# ProProject_PetCareSTM32_MiniSTM32_2024-0.net
KiCad netlist of a schematic drawn in EasyEDA Pro
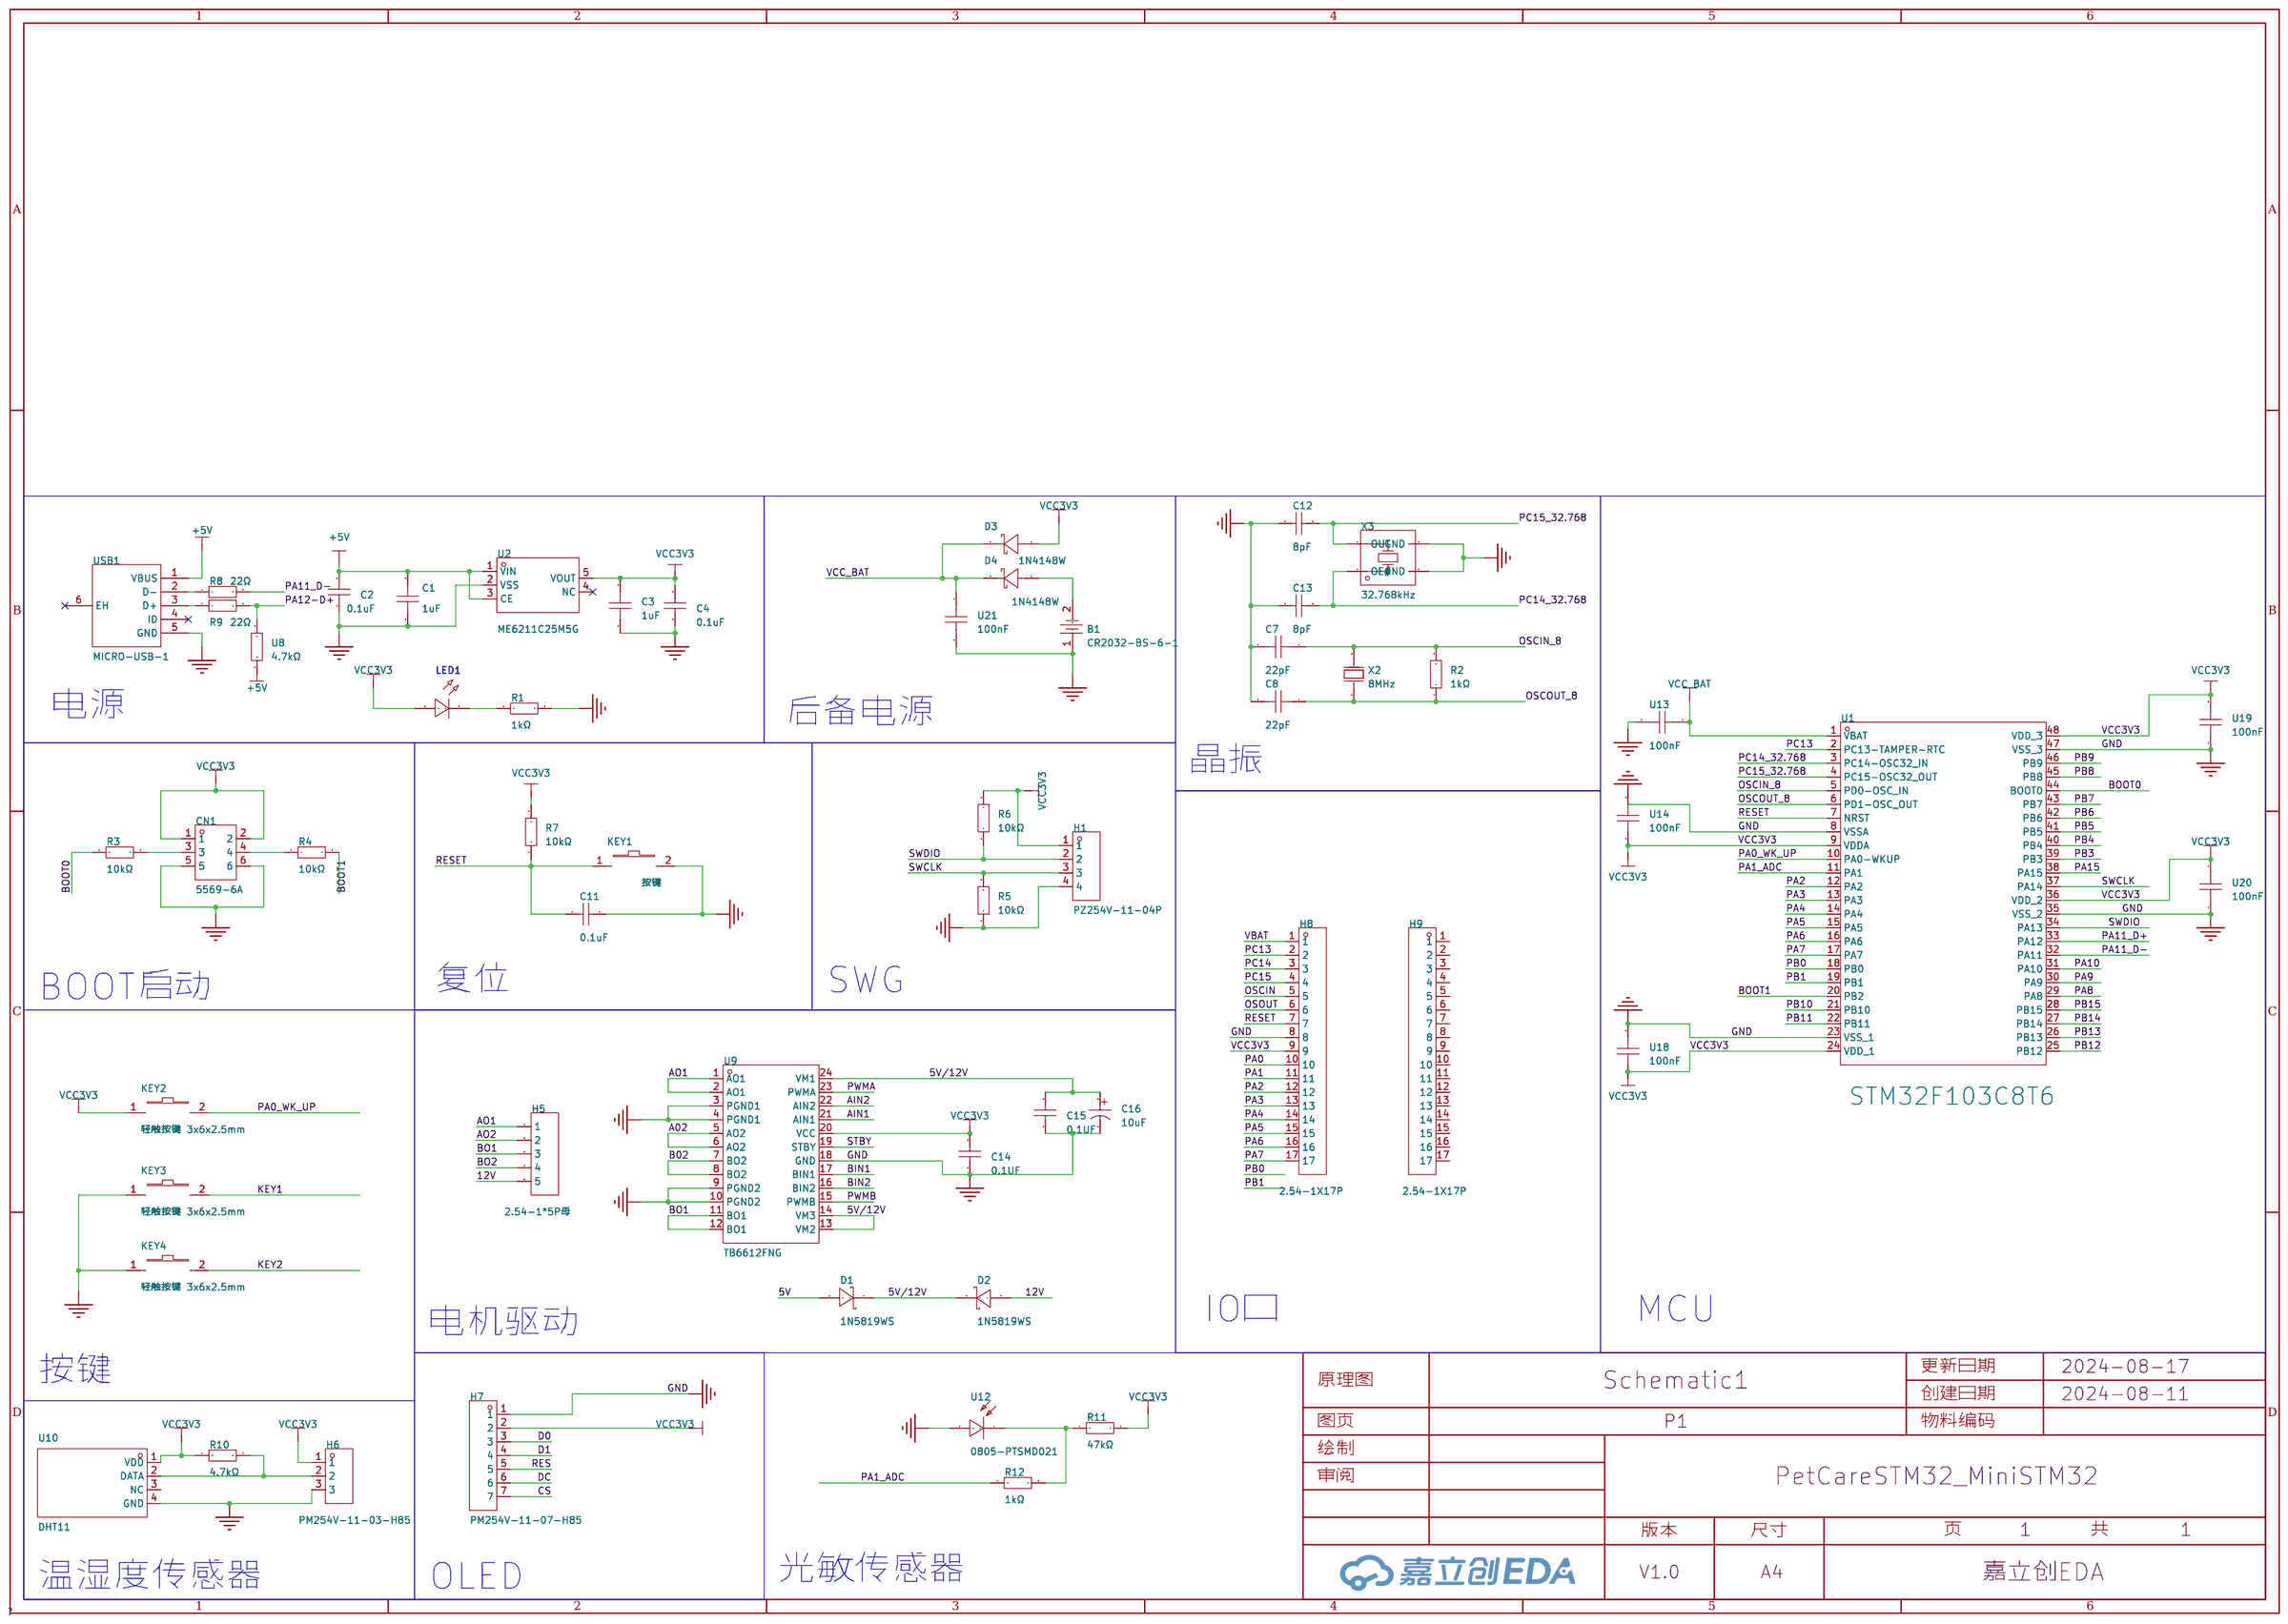
[diagram p0: schematic sheet]

(export (version "E")
  (design (tool "Eeschema 10.0.6"))
  (components
    (comp (ref "B1")
      (value "CR2032-BS-6-1")
      (footprint "easyedapro:BAT-TH_CR2032-BS-6-1")
      (description "连接器类型:电池底座;适用电池规格:CR2032;工作温度范围:-;")
      (fields (field (name "Manufacturer") "Q&J"))
      (libsource (lib "easyedapro") (part "CR2032-BS-6-1"))
    )
    (comp (ref "C1")
      (value "1uF")
      (footprint "easyedapro:C0603")
      (description "容值:1uF;精度:±10%;额定电压:50V;材质(温度系数):X5R;")
      (fields
        (field (name "Manufacturer Part") "CL10A105KB8NNNC")
        (field (name "Manufacturer") "SAMSUNG(三星)")
      )
      (libsource (lib "easyedapro") (part "CL10A105KB8NNNC"))
    )
    (comp (ref "C2")
      (value "0.1uF")
      (footprint "easyedapro:C0603")
      (libsource (lib "easyedapro") (part "CAPCER0.1UF16VX5R0603,CAPCER0.1UF25VX5R0603,CAPCER0.1UF16VX7R0603"))
    )
    (comp (ref "C3")
      (value "1uF")
      (footprint "easyedapro:C0603")
      (description "容值:1uF;精度:±10%;额定电压:50V;材质(温度系数):X5R;")
      (fields
        (field (name "Manufacturer Part") "CL10A105KB8NNNC")
        (field (name "Manufacturer") "SAMSUNG(三星)")
      )
      (libsource (lib "easyedapro") (part "CL10A105KB8NNNC"))
    )
    (comp (ref "C4")
      (value "0.1uF")
      (footprint "easyedapro:C0603")
      (libsource (lib "easyedapro") (part "CAPCER0.1UF16VX5R0603,CAPCER0.1UF25VX5R0603,CAPCER0.1UF16VX7R0603"))
    )
    (comp (ref "C7")
      (value "22pF")
      (footprint "easyedapro:C0603")
      (description "容值:22pF;精度:±5%;额定电压:50V;材质(温度系数):C0G;")
      (fields
        (field (name "Manufacturer Part") "CL10C220JB81PNC")
        (field (name "Manufacturer") "SAMSUNG(三星)")
      )
      (libsource (lib "easyedapro") (part "CL10C220JB81PNC"))
    )
    (comp (ref "C8")
      (value "22pF")
      (footprint "easyedapro:C0603")
      (description "容值:22pF;精度:±5%;额定电压:50V;材质(温度系数):C0G;")
      (fields
        (field (name "Manufacturer Part") "CL10C220JB81PNC")
        (field (name "Manufacturer") "SAMSUNG(三星)")
      )
      (libsource (lib "easyedapro") (part "CL10C220JB81PNC"))
    )
    (comp (ref "C11")
      (value "0.1uF")
      (footprint "easyedapro:C0603")
      (libsource (lib "easyedapro") (part "CAPCER0.1UF16VX5R0603,CAPCER0.1UF25VX5R0603,CAPCER0.1UF16VX7R0603"))
    )
    (comp (ref "C12")
      (value "8pF")
      (footprint "easyedapro:C0603")
      (description "容值:8pF;额定电压:50V;材质(温度系数):C0G;")
      (fields (field (name "Manufacturer Part") "0603CG8R0C500NT") (field (name "Manufacturer") "FH(风华)"))
      (libsource (lib "easyedapro") (part "0603CG8R0C500NT_C36508"))
    )
    (comp (ref "C13")
      (value "8pF")
      (footprint "easyedapro:C0603")
      (description "容值:8pF;额定电压:50V;材质(温度系数):C0G;")
      (fields (field (name "Manufacturer Part") "0603CG8R0C500NT") (field (name "Manufacturer") "FH(风华)"))
      (libsource (lib "easyedapro") (part "0603CG8R0C500NT_C36508"))
    )
    (comp (ref "C14")
      (value "0.1UF")
      (footprint "easyedapro:C0603")
      (libsource (lib "easyedapro") (part "CAPCER0.1UF16VX5R0603,CAPCER0.1UF25VX5R0603,CAPCER0.1UF16VX7R0603"))
    )
    (comp (ref "C15")
      (value "0.1UF")
      (footprint "easyedapro:C0603")
      (libsource (lib "easyedapro") (part "CAPCER0.1UF16VX5R0603,CAPCER0.1UF25VX5R0603,CAPCER0.1UF16VX7R0603"))
    )
    (comp (ref "C16")
      (value "10uF")
      (footprint "easyedapro:CAP-TH_BD5.0-P2.00-D0.8-FD")
      (description "容值:10uF;精度:±20%;额定电压:25V;")
      (fields (field (name "Manufacturer Part") "KF100M025C110A") (field (name "Manufacturer") "CapXon(丰宾)"))
      (libsource (lib "easyedapro") (part "KF100M025C110A"))
    )
    (comp (ref "CN1")
      (value "5569-6A")
      (footprint "easyedapro:CONN-TH_6P-P4.20_5569-6A-1")
      (libsource (lib "easyedapro") (part "5569-6A"))
    )
    (comp (ref "D1")
      (value "1N5819WS")
      (footprint "easyedapro:SOD-323_L1.8-W1.3-LS2.5-RD")
      (description "正向压降(Vf):600mV@1A;直流反向耐压(Vr):40V;平均整流电流(Io):1A;")
      (fields (field (name "Manufacturer") "Hottech(合科泰)"))
      (libsource (lib "easyedapro") (part "1N5819WS"))
    )
    (comp (ref "D2")
      (value "1N5819WS")
      (footprint "easyedapro:SOD-323_L1.8-W1.3-LS2.5-RD")
      (description "正向压降(Vf):600mV@1A;直流反向耐压(Vr):40V;平均整流电流(Io):1A;")
      (fields (field (name "Manufacturer") "Hottech(合科泰)"))
      (libsource (lib "easyedapro") (part "1N5819WS"))
    )
    (comp (ref "D3")
      (value "1N4148W")
      (footprint "easyedapro:SOD-123_L2.7-W1.6-LS3.7-FD")
      (description "二极管配置:独立式;正向压降(Vf):1.25V@150mA;直流反向耐压(Vr):100V;平均整流电流(Io):150mA;功率:400mW;反向恢复时间(trr):4ns;")
      (fields (field (name "Manufacturer") "宏迦橙"))
      (libsource (lib "easyedapro") (part "1N4148W_C7420318"))
    )
    (comp (ref "D4")
      (value "1N4148W")
      (footprint "easyedapro:SOD-123_L2.7-W1.6-LS3.7-FD")
      (description "二极管配置:独立式;正向压降(Vf):1.25V@150mA;直流反向耐压(Vr):100V;平均整流电流(Io):150mA;功率:400mW;反向恢复时间(trr):4ns;")
      (fields (field (name "Manufacturer") "宏迦橙"))
      (libsource (lib "easyedapro") (part "1N4148W_C7420318"))
    )
    (comp (ref "H1")
      (value "PZ254V-11-04P")
      (footprint "easyedapro:HDR-TH_4P-P2.54-V-M")
      (fields (field (name "Manufacturer") "XFCN(兴飞)"))
      (libsource (lib "easyedapro") (part "PZ254V-11-04P_C2691448"))
    )
    (comp (ref "H5")
      (value "2.54-1*5P母")
      (footprint "easyedapro:HDR-TH_5P-P2.54-V-F")
      (description "插孔结构:1x5P;间距:2.54mm;行距:-;安装类型:直插;排数:单排;总孔位数:5P;塑高:-;触头材质:-;触头镀层:-;")
      (fields (field (name "Manufacturer") "BOOMELE(博穆精密)"))
      (libsource (lib "easyedapro") (part "Header-Female-2.54_1x5"))
    )
    (comp (ref "H6")
      (value "PM254V-11-03-H85")
      (footprint "easyedapro:HDR-TH_3P-P2.54-V-F")
      (description "插孔结构:1x3P;间距:2.54mm;行距:-;安装类型:直插;排数:单排;总孔位数:3P;塑高:-;触头材质:黄铜;触头镀层:-;")
      (fields (field (name "Manufacturer") "XFCN(兴飞)"))
      (libsource (lib "easyedapro") (part "PM254V-11-03-H85"))
    )
    (comp (ref "H7")
      (value "PM254V-11-07-H85")
      (footprint "easyedapro:HDR-TH_7P-P2.54-V-F")
      (fields (field (name "Manufacturer") "XFCN(兴飞)"))
      (libsource (lib "easyedapro") (part "PM254V-11-07-H85"))
    )
    (comp (ref "H8")
      (value "2.54-1X17P")
      (footprint "easyedapro:HDR-TH_17P-P2.54-V-M")
      (fields (field (name "Manufacturer") "kinghelm(金航标)"))
      (libsource (lib "easyedapro") (part "KH-2.54PH180-1X17P-L11.5"))
    )
    (comp (ref "H9")
      (value "2.54-1X17P")
      (footprint "easyedapro:HDR-TH_17P-P2.54-V-M")
      (fields (field (name "Manufacturer") "kinghelm(金航标)"))
      (libsource (lib "easyedapro") (part "KH-2.54PH180-1X17P-L11.5"))
    )
    (comp (ref "KEY1")
      (value "按键")
      (footprint "easyedapro:SW-SMD_L6.0-W3.6-LS8.0")
      (libsource (lib "easyedapro") (part "3x6x2.5mm"))
    )
    (comp (ref "KEY2")
      (value "轻触按键 3x6x2.5mm")
      (footprint "easyedapro:SW-SMD_L6.0-W3.6-LS8.0")
      (libsource (lib "easyedapro") (part "3x6x2.5mm"))
    )
    (comp (ref "KEY3")
      (value "轻触按键 3x6x2.5mm")
      (footprint "easyedapro:SW-SMD_L6.0-W3.6-LS8.0")
      (libsource (lib "easyedapro") (part "3x6x2.5mm"))
    )
    (comp (ref "KEY4")
      (value "轻触按键 3x6x2.5mm")
      (footprint "easyedapro:SW-SMD_L6.0-W3.6-LS8.0")
      (libsource (lib "easyedapro") (part "3x6x2.5mm"))
    )
    (comp (ref "LED1")
      (value "~")
      (footprint "easyedapro:LED_0805")
      (libsource (lib "easyedapro") (part "LED_B"))
    )
    (comp (ref "R1")
      (value "1kΩ")
      (footprint "easyedapro:R0603")
      (description "电阻类型:厚膜电阻;阻值:1kΩ;精度:±1%;功率:100mW;最大工作电压:75V;温度系数:±100ppm/°C;")
      (fields (field (name "Manufacturer Part") "RC0603FR-071KL") (field (name "Manufacturer") "YAGEO(国巨)"))
      (libsource (lib "easyedapro") (part "RC0603FR-071KL"))
    )
    (comp (ref "R2")
      (value "1kΩ")
      (footprint "easyedapro:R0603")
      (description "电阻类型:厚膜电阻;阻值:1kΩ;精度:±0.5%;功率:100mW;最大工作电压:75V;温度系数:±100ppm/°C;")
      (fields
        (field (name "Manufacturer Part") "0603WAD1001T5E")
        (field (name "Manufacturer") "UNI-ROYAL(厚声)")
      )
      (libsource (lib "easyedapro") (part "0603WAD1001T5E"))
    )
    (comp (ref "R3")
      (value "10kΩ")
      (footprint "easyedapro:R0603")
      (description "电阻类型:厚膜电阻;阻值:10kΩ;精度:±1%;功率:100mW;最大工作电压:75V;温度系数:±100ppm/°C;")
      (fields
        (field (name "Manufacturer Part") "0603WAF1002T5E")
        (field (name "Manufacturer") "UNI-ROYAL(厚声)")
      )
      (libsource (lib "easyedapro") (part "0603WAF1002T5E"))
    )
    (comp (ref "R4")
      (value "10kΩ")
      (footprint "easyedapro:R0603")
      (description "电阻类型:厚膜电阻;阻值:10kΩ;精度:±1%;功率:100mW;最大工作电压:75V;温度系数:±100ppm/°C;")
      (fields
        (field (name "Manufacturer Part") "0603WAF1002T5E")
        (field (name "Manufacturer") "UNI-ROYAL(厚声)")
      )
      (libsource (lib "easyedapro") (part "0603WAF1002T5E"))
    )
    (comp (ref "R5")
      (value "10kΩ")
      (footprint "easyedapro:R0603")
      (description "电阻类型:厚膜电阻;阻值:10kΩ;精度:±1%;功率:100mW;最大工作电压:75V;温度系数:±100ppm/°C;")
      (fields
        (field (name "Manufacturer Part") "0603WAF1002T5E")
        (field (name "Manufacturer") "UNI-ROYAL(厚声)")
      )
      (libsource (lib "easyedapro") (part "0603WAF1002T5E"))
    )
    (comp (ref "R6")
      (value "10kΩ")
      (footprint "easyedapro:R0603")
      (description "电阻类型:厚膜电阻;阻值:10kΩ;精度:±1%;功率:100mW;最大工作电压:75V;温度系数:±100ppm/°C;")
      (fields
        (field (name "Manufacturer Part") "0603WAF1002T5E")
        (field (name "Manufacturer") "UNI-ROYAL(厚声)")
      )
      (libsource (lib "easyedapro") (part "0603WAF1002T5E"))
    )
    (comp (ref "R7")
      (value "10kΩ")
      (footprint "easyedapro:R0603")
      (description "电阻类型:厚膜电阻;阻值:10kΩ;精度:±1%;功率:100mW;最大工作电压:75V;温度系数:±100ppm/°C;")
      (fields
        (field (name "Manufacturer Part") "0603WAF1002T5E")
        (field (name "Manufacturer") "UNI-ROYAL(厚声)")
      )
      (libsource (lib "easyedapro") (part "0603WAF1002T5E"))
    )
    (comp (ref "R8")
      (value "22Ω")
      (footprint "easyedapro:R0805")
      (description "电阻类型:薄膜电阻;阻值:22Ω;精度:±1%;功率:250mW;最大工作电压:150V;温度系数:±25ppm/°C;")
      (fields
        (field (name "Manufacturer Part") "TC0525F220JT5E")
        (field (name "Manufacturer") "UNI-ROYAL(厚声)")
      )
      (libsource (lib "easyedapro") (part "TC0525F220JT5E"))
    )
    (comp (ref "R9")
      (value "22Ω")
      (footprint "easyedapro:R0805")
      (description "电阻类型:薄膜电阻;阻值:22Ω;精度:±1%;功率:250mW;最大工作电压:150V;温度系数:±25ppm/°C;")
      (fields
        (field (name "Manufacturer Part") "TC0525F220JT5E")
        (field (name "Manufacturer") "UNI-ROYAL(厚声)")
      )
      (libsource (lib "easyedapro") (part "TC0525F220JT5E"))
    )
    (comp (ref "R10")
      (value "4.7kΩ")
      (footprint "easyedapro:R1206")
      (description "电阻类型:厚膜电阻;阻值:4.7kΩ;精度:±1%;功率:250mW;最大工作电压:200V;温度系数:±100ppm/°C;")
      (fields
        (field (name "Manufacturer Part") "1206W4F4701T5E")
        (field (name "Manufacturer") "UNI-ROYAL(厚声)")
      )
      (libsource (lib "easyedapro") (part "1206W4F4701T5E"))
    )
    (comp (ref "R11")
      (value "47kΩ")
      (footprint "easyedapro:R0805")
      (description "电阻类型:厚膜电阻;阻值:47kΩ;精度:±1%;功率:125mW;最大工作电压:150V;温度系数:±100ppm/°C;")
      (fields
        (field (name "Manufacturer Part") "0805W8F4702T5E")
        (field (name "Manufacturer") "UNI-ROYAL(厚声)")
      )
      (libsource (lib "easyedapro") (part "0805W8F4702T5E"))
    )
    (comp (ref "R12")
      (value "1kΩ")
      (footprint "easyedapro:R0603")
      (description "电阻类型:厚膜电阻;阻值:1kΩ;精度:±1%;功率:100mW;最大工作电压:75V;温度系数:±100ppm/°C;")
      (fields (field (name "Manufacturer Part") "RC0603FR-071KL") (field (name "Manufacturer") "YAGEO(国巨)"))
      (libsource (lib "easyedapro") (part "RC0603FR-071KL"))
    )
    (comp (ref "U1")
      (value "STM32F103C8T6")
      (footprint "easyedapro:LQFP-48_L7.0-W7.0-P0.50-LS9.0-BL")
      (description "CPU内核:ARM-M3;程序存储容量:64KB;RAM总容量:20KB;GPIO端口数量:37;工作电压范围:2V~3.6V;CPU最大主频:72MHz;程序存储器类型:FLASH;")
      (fields (field (name "Manufacturer") "ST(意法半导体)"))
      (libsource (lib "easyedapro") (part "STM32F103C8T6"))
    )
    (comp (ref "U2")
      (value "ME6211C25M5G")
      (footprint "easyedapro:SOT-23-5_L2.9-W1.7-P0.95-LS2.8-BL")
      (fields (field (name "Manufacturer") "MICRONE(南京微盟)"))
      (libsource (lib "easyedapro") (part "ME6211C25M5G"))
    )
    (comp (ref "U8")
      (value "4.7kΩ")
      (footprint "easyedapro:R0603")
      (description "电阻类型:薄膜电阻;阻值:4.7kΩ;精度:±1%;功率:100mW;最大工作电压:75V;温度系数:±50ppm/°C;")
      (fields (field (name "Manufacturer Part") "AR03FTDX4701A") (field (name "Manufacturer") "Viking(光颉)"))
      (libsource (lib "easyedapro") (part "AR03FTDX4701A"))
    )
    (comp (ref "U9")
      (value "TB6612FNG")
      (footprint "easyedapro:SSOP-24_L8.4-W5.8-P0.65-LS7.8-BL")
      (description "双直流电机驱动器集成电路")
      (fields (field (name "Manufacturer") "TOSHIBA(东芝)"))
      (libsource (lib "easyedapro") (part "TB6612FNG(O,C,8,EL"))
    )
    (comp (ref "U10")
      (value "DHT11")
      (footprint "easyedapro:SENSOR-TH_DHT11")
      (description "新款电容式数字温湿度传感器,老款已停产16.1x12.6x5.8mm")
      (fields (field (name "Manufacturer") "广州奥松"))
      (libsource (lib "easyedapro") (part "DHT11"))
    )
    (comp (ref "U12")
      (value "0805-PTSMD021")
      (footprint "easyedapro:OPTO-SMD_L2.0-W1.3_RPM-075PTT86")
      (fields (field (name "Manufacturer") "JCHL(晶创和立)"))
      (libsource (lib "easyedapro") (part "0805-PTSM D021"))
    )
    (comp (ref "U13")
      (value "100nF")
      (footprint "easyedapro:C0603")
      (description "容值:100nF;精度:±10%;额定电压:50V;材质(温度系数):X7R;")
      (fields
        (field (name "Manufacturer Part") "CGA0603X7R104K500JT")
        (field (name "Manufacturer") "HRE(芯声)")
      )
      (libsource (lib "easyedapro") (part "CGA0603X7R104K500JT"))
    )
    (comp (ref "U14")
      (value "100nF")
      (footprint "easyedapro:C0603")
      (description "容值:100nF;精度:±10%;额定电压:50V;材质(温度系数):X7R;")
      (fields
        (field (name "Manufacturer Part") "CGA0603X7R104K500JT")
        (field (name "Manufacturer") "HRE(芯声)")
      )
      (libsource (lib "easyedapro") (part "CGA0603X7R104K500JT"))
    )
    (comp (ref "U18")
      (value "100nF")
      (footprint "easyedapro:C0603")
      (description "容值:100nF;精度:±10%;额定电压:50V;材质(温度系数):X7R;")
      (fields
        (field (name "Manufacturer Part") "CGA0603X7R104K500JT")
        (field (name "Manufacturer") "HRE(芯声)")
      )
      (libsource (lib "easyedapro") (part "CGA0603X7R104K500JT"))
    )
    (comp (ref "U19")
      (value "100nF")
      (footprint "easyedapro:C0603")
      (description "容值:100nF;精度:±10%;额定电压:50V;材质(温度系数):X7R;")
      (fields
        (field (name "Manufacturer Part") "CGA0603X7R104K500JT")
        (field (name "Manufacturer") "HRE(芯声)")
      )
      (libsource (lib "easyedapro") (part "CGA0603X7R104K500JT"))
    )
    (comp (ref "U20")
      (value "100nF")
      (footprint "easyedapro:C0603")
      (description "容值:100nF;精度:±10%;额定电压:50V;材质(温度系数):X7R;")
      (fields
        (field (name "Manufacturer Part") "CGA0603X7R104K500JT")
        (field (name "Manufacturer") "HRE(芯声)")
      )
      (libsource (lib "easyedapro") (part "CGA0603X7R104K500JT"))
    )
    (comp (ref "U21")
      (value "100nF")
      (footprint "easyedapro:C0603")
      (description "容值:100nF;精度:±10%;额定电压:50V;材质(温度系数):X7R;")
      (fields
        (field (name "Manufacturer Part") "CGA0603X7R104K500JT")
        (field (name "Manufacturer") "HRE(芯声)")
      )
      (libsource (lib "easyedapro") (part "CGA0603X7R104K500JT"))
    )
    (comp (ref "USB1")
      (value "MICRO-USB-1")
      (footprint "easyedapro:MICRO-USB-SMD_C9900008946")
      (libsource (lib "easyedapro") (part "MICRO-USB-1"))
    )
    (comp (ref "X2")
      (value "8MHz")
      (footprint "easyedapro:OSC-SMD_L5.0-W3.2")
      (description "晶振类型:贴片晶振;频率:8MHz;常温频差:±20ppm;外接负载电容:18pF;频率稳定度(全温):±30ppm;")
      (fields
        (field (name "Manufacturer Part") "ABM3-8.000MHZ-D2Y-T")
        (field (name "Manufacturer") "ABRACON")
      )
      (libsource (lib "easyedapro") (part "ABM3-8.000MHZ-D2Y-T"))
    )
    (comp (ref "X3")
      (value "32.768kHz")
      (footprint "easyedapro:CRYSTAL-SMD_4P-L8.0-W3.8-BL")
      (description "晶振类型:-;频率:32.768kHz;常温频差:±20ppm;外接负载电容:12.5pF;频率稳定度(全温):-;")
      (fields (field (name "Manufacturer Part") "ABS25-32.768KHZ-T") (field (name "Manufacturer") "ABRACON"))
      (libsource (lib "easyedapro") (part "ABS25-32.768KHZ-T"))
    )
  )
  (nets
    (net (code "1") (name "+5V") (class "Default")
      (node (ref "C1") (pin "2") (pinfunction "2_2") (pintype "unspecified"))
      (node (ref "C2") (pin "2") (pinfunction "2_2") (pintype "input"))
      (node (ref "U2") (pin "1") (pinfunction "VIN_1") (pintype "unspecified"))
      (node (ref "U2") (pin "3") (pinfunction "CE_3") (pintype "unspecified"))
      (node (ref "U8") (pin "1") (pinfunction "1_1") (pintype "unspecified"))
      (node (ref "USB1") (pin "1") (pinfunction "VBUS_1") (pintype "input"))
    )
    (net (code "2") (name "/5V") (class "Default")
      (node (ref "D1") (pin "2") (pinfunction "A_2") (pintype "unspecified"))
    )
    (net (code "3") (name "/5V{slash}12V") (class "Default")
      (node (ref "C15") (pin "2") (pinfunction "2_2") (pintype "input"))
      (node (ref "C16") (pin "1") (pinfunction "1_1") (pintype "input"))
      (node (ref "D1") (pin "1") (pinfunction "K_1") (pintype "unspecified"))
      (node (ref "D2") (pin "1") (pinfunction "K_1") (pintype "unspecified"))
      (node (ref "U9") (pin "13") (pinfunction "VM2_13") (pintype "unspecified"))
      (node (ref "U9") (pin "14") (pinfunction "VM3_14") (pintype "unspecified"))
      (node (ref "U9") (pin "24") (pinfunction "VM1_24") (pintype "unspecified"))
    )
    (net (code "4") (name "/12V") (class "Default")
      (node (ref "D2") (pin "2") (pinfunction "A_2") (pintype "unspecified"))
      (node (ref "H5") (pin "5") (pinfunction "5_5") (pintype "input"))
    )
    (net (code "5") (name "/A02") (class "Default")
      (node (ref "U9") (pin "5") (pinfunction "AO2_5") (pintype "unspecified"))
      (node (ref "U9") (pin "6") (pinfunction "AO2_6") (pintype "unspecified"))
    )
    (net (code "6") (name "/AIN1") (class "Default")
      (node (ref "U9") (pin "21") (pinfunction "AIN1_21") (pintype "unspecified"))
    )
    (net (code "7") (name "/AIN2") (class "Default")
      (node (ref "U9") (pin "22") (pinfunction "AIN2_22") (pintype "unspecified"))
    )
    (net (code "8") (name "/AO1") (class "Default")
      (node (ref "H5") (pin "1") (pinfunction "1_1") (pintype "input"))
      (node (ref "U9") (pin "1") (pinfunction "AO1_1") (pintype "unspecified"))
      (node (ref "U9") (pin "2") (pinfunction "AO1_2") (pintype "unspecified"))
    )
    (net (code "9") (name "/AO2") (class "Default")
      (node (ref "H5") (pin "2") (pinfunction "2_2") (pintype "input"))
    )
    (net (code "10") (name "/B02") (class "Default")
      (node (ref "U9") (pin "7") (pinfunction "BO2_7") (pintype "unspecified"))
      (node (ref "U9") (pin "8") (pinfunction "BO2_8") (pintype "unspecified"))
    )
    (net (code "11") (name "/BIN1") (class "Default")
      (node (ref "U9") (pin "17") (pinfunction "BIN1_17") (pintype "unspecified"))
    )
    (net (code "12") (name "/BIN2") (class "Default")
      (node (ref "U9") (pin "16") (pinfunction "BIN2_16") (pintype "unspecified"))
    )
    (net (code "13") (name "/BO1") (class "Default")
      (node (ref "H5") (pin "3") (pinfunction "3_3") (pintype "input"))
      (node (ref "U9") (pin "11") (pinfunction "BO1_11") (pintype "unspecified"))
      (node (ref "U9") (pin "12") (pinfunction "BO1_12") (pintype "unspecified"))
    )
    (net (code "14") (name "/BO2") (class "Default")
      (node (ref "H5") (pin "4") (pinfunction "4_4") (pintype "input"))
    )
    (net (code "15") (name "/BOOT0") (class "Default")
      (node (ref "R3") (pin "1") (pinfunction "1_1") (pintype "input"))
      (node (ref "U1") (pin "44") (pinfunction "BOOT0_44") (pintype "unspecified"))
    )
    (net (code "16") (name "/BOOT1") (class "Default")
      (node (ref "R4") (pin "2") (pinfunction "2_2") (pintype "input"))
      (node (ref "U1") (pin "20") (pinfunction "PB2_20") (pintype "unspecified"))
    )
    (net (code "17") (name "/CS") (class "Default")
      (node (ref "H7") (pin "7") (pinfunction "7_7") (pintype "unspecified"))
    )
    (net (code "18") (name "/D0") (class "Default")
      (node (ref "H7") (pin "3") (pinfunction "3_3") (pintype "unspecified"))
    )
    (net (code "19") (name "/D1") (class "Default")
      (node (ref "H7") (pin "4") (pinfunction "4_4") (pintype "unspecified"))
    )
    (net (code "20") (name "/DC") (class "Default")
      (node (ref "H7") (pin "6") (pinfunction "6_6") (pintype "unspecified"))
    )
    (net (code "21") (name "/KEY1") (class "Default")
      (node (ref "KEY3") (pin "2") (pinfunction "2_2") (pintype "input"))
    )
    (net (code "22") (name "/KEY2") (class "Default")
      (node (ref "KEY4") (pin "2") (pinfunction "2_2") (pintype "input"))
    )
    (net (code "23") (name "/OSCIN") (class "Default")
      (node (ref "H8") (pin "5") (pinfunction "5_5") (pintype "unspecified"))
    )
    (net (code "24") (name "/OSCIN_8") (class "Default")
      (node (ref "C7") (pin "1") (pinfunction "1_1") (pintype "unspecified"))
      (node (ref "R2") (pin "2") (pinfunction "2_2") (pintype "input"))
      (node (ref "U1") (pin "5") (pinfunction "PD0-OSC_IN_5") (pintype "unspecified"))
      (node (ref "X2") (pin "2") (pinfunction "OSC2_2") (pintype "input"))
    )
    (net (code "25") (name "/OSCOUT_8") (class "Default")
      (node (ref "C8") (pin "1") (pinfunction "1_1") (pintype "unspecified"))
      (node (ref "R2") (pin "1") (pinfunction "1_1") (pintype "input"))
      (node (ref "U1") (pin "6") (pinfunction "PD1-OSC_OUT_6") (pintype "unspecified"))
      (node (ref "X2") (pin "1") (pinfunction "OSC1_1") (pintype "input"))
    )
    (net (code "26") (name "/OSOUT") (class "Default")
      (node (ref "H8") (pin "6") (pinfunction "6_6") (pintype "unspecified"))
    )
    (net (code "27") (name "/PA0") (class "Default")
      (node (ref "H8") (pin "10") (pinfunction "10_10") (pintype "unspecified"))
    )
    (net (code "28") (name "/PA0_WK_UP") (class "Default")
      (node (ref "KEY2") (pin "2") (pinfunction "2_2") (pintype "input"))
      (node (ref "U1") (pin "10") (pinfunction "PA0-WKUP_10") (pintype "unspecified"))
    )
    (net (code "29") (name "/PA1") (class "Default")
      (node (ref "H8") (pin "11") (pinfunction "11_11") (pintype "unspecified"))
    )
    (net (code "30") (name "/PA1_ADC") (class "Default")
      (node (ref "R12") (pin "1") (pinfunction "1_1") (pintype "input"))
      (node (ref "U1") (pin "11") (pinfunction "PA1_11") (pintype "unspecified"))
    )
    (net (code "31") (name "/PA2") (class "Default")
      (node (ref "H8") (pin "12") (pinfunction "12_12") (pintype "unspecified"))
      (node (ref "U1") (pin "12") (pinfunction "PA2_12") (pintype "unspecified"))
    )
    (net (code "32") (name "/PA3") (class "Default")
      (node (ref "H8") (pin "13") (pinfunction "13_13") (pintype "unspecified"))
      (node (ref "U1") (pin "13") (pinfunction "PA3_13") (pintype "unspecified"))
    )
    (net (code "33") (name "/PA4") (class "Default")
      (node (ref "H8") (pin "14") (pinfunction "14_14") (pintype "unspecified"))
      (node (ref "U1") (pin "14") (pinfunction "PA4_14") (pintype "unspecified"))
    )
    (net (code "34") (name "/PA5") (class "Default")
      (node (ref "H8") (pin "15") (pinfunction "15_15") (pintype "unspecified"))
      (node (ref "U1") (pin "15") (pinfunction "PA5_15") (pintype "unspecified"))
    )
    (net (code "35") (name "/PA6") (class "Default")
      (node (ref "H8") (pin "16") (pinfunction "16_16") (pintype "unspecified"))
      (node (ref "U1") (pin "16") (pinfunction "PA6_16") (pintype "unspecified"))
    )
    (net (code "36") (name "/PA7") (class "Default")
      (node (ref "H8") (pin "17") (pinfunction "17_17") (pintype "unspecified"))
      (node (ref "U1") (pin "17") (pinfunction "PA7_17") (pintype "unspecified"))
    )
    (net (code "37") (name "/PA8") (class "Default")
      (node (ref "U1") (pin "29") (pinfunction "PA8_29") (pintype "unspecified"))
    )
    (net (code "38") (name "/PA9") (class "Default")
      (node (ref "U1") (pin "30") (pinfunction "PA9_30") (pintype "unspecified"))
    )
    (net (code "39") (name "/PA10") (class "Default")
      (node (ref "U1") (pin "31") (pinfunction "PA10_31") (pintype "unspecified"))
    )
    (net (code "40") (name "/PA11_D+") (class "Default")
      (node (ref "U1") (pin "33") (pinfunction "PA12_33") (pintype "unspecified"))
    )
    (net (code "41") (name "/PA11_D-") (class "Default")
      (node (ref "R8") (pin "2") (pinfunction "2_2") (pintype "input"))
      (node (ref "U1") (pin "32") (pinfunction "PA11_32") (pintype "unspecified"))
    )
    (net (code "42") (name "/PA12-D+") (class "Default")
      (node (ref "R9") (pin "2") (pinfunction "2_2") (pintype "input"))
      (node (ref "U8") (pin "2") (pinfunction "2_2") (pintype "unspecified"))
    )
    (net (code "43") (name "/PA15") (class "Default")
      (node (ref "U1") (pin "38") (pinfunction "PA15_38") (pintype "unspecified"))
    )
    (net (code "44") (name "/PB0") (class "Default")
      (node (ref "U1") (pin "18") (pinfunction "PB0_18") (pintype "unspecified"))
    )
    (net (code "45") (name "/PB1") (class "Default")
      (node (ref "U1") (pin "19") (pinfunction "PB1_19") (pintype "unspecified"))
    )
    (net (code "46") (name "/PB3") (class "Default")
      (node (ref "U1") (pin "39") (pinfunction "PB3_39") (pintype "unspecified"))
    )
    (net (code "47") (name "/PB4") (class "Default")
      (node (ref "U1") (pin "40") (pinfunction "PB4_40") (pintype "unspecified"))
    )
    (net (code "48") (name "/PB5") (class "Default")
      (node (ref "U1") (pin "41") (pinfunction "PB5_41") (pintype "unspecified"))
    )
    (net (code "49") (name "/PB6") (class "Default")
      (node (ref "U1") (pin "42") (pinfunction "PB6_42") (pintype "unspecified"))
    )
    (net (code "50") (name "/PB7") (class "Default")
      (node (ref "U1") (pin "43") (pinfunction "PB7_43") (pintype "unspecified"))
    )
    (net (code "51") (name "/PB8") (class "Default")
      (node (ref "U1") (pin "45") (pinfunction "PB8_45") (pintype "unspecified"))
    )
    (net (code "52") (name "/PB9") (class "Default")
      (node (ref "U1") (pin "46") (pinfunction "PB9_46") (pintype "unspecified"))
    )
    (net (code "53") (name "/PB10") (class "Default")
      (node (ref "U1") (pin "21") (pinfunction "PB10_21") (pintype "unspecified"))
    )
    (net (code "54") (name "/PB11") (class "Default")
      (node (ref "U1") (pin "22") (pinfunction "PB11_22") (pintype "unspecified"))
    )
    (net (code "55") (name "/PB12") (class "Default")
      (node (ref "U1") (pin "25") (pinfunction "PB12_25") (pintype "unspecified"))
    )
    (net (code "56") (name "/PB13") (class "Default")
      (node (ref "U1") (pin "26") (pinfunction "PB13_26") (pintype "unspecified"))
    )
    (net (code "57") (name "/PB14") (class "Default")
      (node (ref "U1") (pin "27") (pinfunction "PB14_27") (pintype "unspecified"))
    )
    (net (code "58") (name "/PB15") (class "Default")
      (node (ref "U1") (pin "28") (pinfunction "PB15_28") (pintype "unspecified"))
    )
    (net (code "59") (name "/PC13") (class "Default")
      (node (ref "H8") (pin "2") (pinfunction "2_2") (pintype "unspecified"))
      (node (ref "U1") (pin "2") (pinfunction "PC13-TAMPER-RTC_2") (pintype "unspecified"))
    )
    (net (code "60") (name "/PC14") (class "Default")
      (node (ref "H8") (pin "3") (pinfunction "3_3") (pintype "unspecified"))
    )
    (net (code "61") (name "/PC14_32.768") (class "Default")
      (node (ref "C13") (pin "2") (pinfunction "2_2") (pintype "input"))
      (node (ref "U1") (pin "3") (pinfunction "PC14-OSC32_IN_3") (pintype "unspecified"))
      (node (ref "X3") (pin "1") (pinfunction "OE#_1") (pintype "input"))
    )
    (net (code "62") (name "/PC15") (class "Default")
      (node (ref "H8") (pin "4") (pinfunction "4_4") (pintype "unspecified"))
    )
    (net (code "63") (name "/PC15_32.768") (class "Default")
      (node (ref "C12") (pin "2") (pinfunction "2_2") (pintype "input"))
      (node (ref "U1") (pin "4") (pinfunction "PC15-OSC32_OUT_4") (pintype "unspecified"))
      (node (ref "X3") (pin "4") (pinfunction "OUT_4") (pintype "input"))
    )
    (net (code "64") (name "/PWMA") (class "Default")
      (node (ref "U9") (pin "23") (pinfunction "PWMA_23") (pintype "unspecified"))
    )
    (net (code "65") (name "/PWMB") (class "Default")
      (node (ref "U9") (pin "15") (pinfunction "PWMB_15") (pintype "unspecified"))
    )
    (net (code "66") (name "/RES") (class "Default")
      (node (ref "H7") (pin "5") (pinfunction "5_5") (pintype "unspecified"))
    )
    (net (code "67") (name "/RESET") (class "Default")
      (node (ref "C11") (pin "1") (pinfunction "1_1") (pintype "input"))
      (node (ref "H8") (pin "7") (pinfunction "7_7") (pintype "unspecified"))
      (node (ref "KEY1") (pin "1") (pinfunction "1_1") (pintype "input"))
      (node (ref "R7") (pin "1") (pinfunction "1_1") (pintype "input"))
      (node (ref "U1") (pin "7") (pinfunction "NRST_7") (pintype "unspecified"))
    )
    (net (code "68") (name "/STBY") (class "Default")
      (node (ref "U9") (pin "19") (pinfunction "STBY_19") (pintype "unspecified"))
    )
    (net (code "69") (name "/SWCLK") (class "Default")
      (node (ref "H1") (pin "3") (pinfunction "3_3") (pintype "unspecified"))
      (node (ref "R5") (pin "2") (pinfunction "2_2") (pintype "input"))
      (node (ref "U1") (pin "37") (pinfunction "PA14_37") (pintype "unspecified"))
    )
    (net (code "70") (name "/SWDIO") (class "Default")
      (node (ref "H1") (pin "2") (pinfunction "2_2") (pintype "unspecified"))
      (node (ref "R6") (pin "1") (pinfunction "1_1") (pintype "input"))
      (node (ref "U1") (pin "34") (pinfunction "PA13_34") (pintype "unspecified"))
    )
    (net (code "71") (name "/VBAT") (class "Default")
      (node (ref "H8") (pin "1") (pinfunction "1_1") (pintype "unspecified"))
    )
    (net (code "72") (name "GND") (class "Default")
      (node (ref "B1") (pin "1") (pinfunction "1_1") (pintype "input"))
      (node (ref "C1") (pin "1") (pinfunction "1_1") (pintype "unspecified"))
      (node (ref "C11") (pin "2") (pinfunction "2_2") (pintype "input"))
      (node (ref "C12") (pin "1") (pinfunction "1_1") (pintype "input"))
      (node (ref "C13") (pin "1") (pinfunction "1_1") (pintype "input"))
      (node (ref "C14") (pin "1") (pinfunction "1_1") (pintype "input"))
      (node (ref "C15") (pin "1") (pinfunction "1_1") (pintype "input"))
      (node (ref "C16") (pin "2") (pinfunction "2_2") (pintype "input"))
      (node (ref "C2") (pin "1") (pinfunction "1_1") (pintype "input"))
      (node (ref "C3") (pin "1") (pinfunction "1_1") (pintype "unspecified"))
      (node (ref "C4") (pin "1") (pinfunction "1_1") (pintype "input"))
      (node (ref "C7") (pin "2") (pinfunction "2_2") (pintype "unspecified"))
      (node (ref "C8") (pin "2") (pinfunction "2_2") (pintype "unspecified"))
      (node (ref "CN1") (pin "5") (pinfunction "5_5") (pintype "unspecified"))
      (node (ref "CN1") (pin "6") (pinfunction "6_6") (pintype "unspecified"))
      (node (ref "H1") (pin "4") (pinfunction "4_4") (pintype "unspecified"))
      (node (ref "H6") (pin "3") (pinfunction "3_3") (pintype "unspecified"))
      (node (ref "H7") (pin "1") (pinfunction "1_1") (pintype "unspecified"))
      (node (ref "H8") (pin "8") (pinfunction "8_8") (pintype "unspecified"))
      (node (ref "KEY1") (pin "2") (pinfunction "2_2") (pintype "input"))
      (node (ref "KEY3") (pin "1") (pinfunction "1_1") (pintype "input"))
      (node (ref "KEY4") (pin "1") (pinfunction "1_1") (pintype "input"))
      (node (ref "R1") (pin "2") (pinfunction "2_2") (pintype "input"))
      (node (ref "R5") (pin "1") (pinfunction "1_1") (pintype "input"))
      (node (ref "U1") (pin "23") (pinfunction "VSS_1_23") (pintype "unspecified"))
      (node (ref "U1") (pin "35") (pinfunction "VSS_2_35") (pintype "unspecified"))
      (node (ref "U1") (pin "47") (pinfunction "VSS_3_47") (pintype "unspecified"))
      (node (ref "U1") (pin "8") (pinfunction "VSSA_8") (pintype "unspecified"))
      (node (ref "U10") (pin "4") (pinfunction "GND_4") (pintype "unspecified"))
      (node (ref "U12") (pin "2") (pinfunction "C_2") (pintype "unspecified"))
      (node (ref "U13") (pin "2") (pinfunction "2_2") (pintype "unspecified"))
      (node (ref "U14") (pin "2") (pinfunction "2_2") (pintype "unspecified"))
      (node (ref "U18") (pin "2") (pinfunction "2_2") (pintype "unspecified"))
      (node (ref "U19") (pin "1") (pinfunction "1_1") (pintype "unspecified"))
      (node (ref "U2") (pin "2") (pinfunction "VSS_2") (pintype "unspecified"))
      (node (ref "U20") (pin "1") (pinfunction "1_1") (pintype "unspecified"))
      (node (ref "U21") (pin "2") (pinfunction "2_2") (pintype "unspecified"))
      (node (ref "U9") (pin "10") (pinfunction "PGND2_10") (pintype "unspecified"))
      (node (ref "U9") (pin "18") (pinfunction "GND_18") (pintype "unspecified"))
      (node (ref "U9") (pin "3") (pinfunction "PGND1_3") (pintype "unspecified"))
      (node (ref "U9") (pin "4") (pinfunction "PGND1_4") (pintype "unspecified"))
      (node (ref "U9") (pin "9") (pinfunction "PGND2_9") (pintype "unspecified"))
      (node (ref "USB1") (pin "5") (pinfunction "GND_5") (pintype "input"))
      (node (ref "X3") (pin "2") (pinfunction "GND_2") (pintype "input"))
      (node (ref "X3") (pin "3") (pinfunction "GND_3") (pintype "input"))
    )
    (net (code "73") (name "Net-(CN1-Pad3)") (class "Default")
      (node (ref "CN1") (pin "3") (pinfunction "3_3") (pintype "unspecified"))
      (node (ref "R3") (pin "2") (pinfunction "2_2") (pintype "input"))
    )
    (net (code "74") (name "Net-(CN1-Pad4)") (class "Default")
      (node (ref "CN1") (pin "4") (pinfunction "4_4") (pintype "unspecified"))
      (node (ref "R4") (pin "1") (pinfunction "1_1") (pintype "input"))
    )
    (net (code "75") (name "Net-(D4-A)") (class "Default")
      (node (ref "B1") (pin "2") (pinfunction "2_2") (pintype "input"))
      (node (ref "D4") (pin "1") (pinfunction "A_1") (pintype "unspecified"))
    )
    (net (code "76") (name "Net-(LED1-C)") (class "Default")
      (node (ref "LED1") (pin "1") (pinfunction "C_1") (pintype "input"))
      (node (ref "R1") (pin "1") (pinfunction "1_1") (pintype "input"))
    )
    (net (code "77") (name "Net-(U10-DATA)") (class "Default")
      (node (ref "H6") (pin "2") (pinfunction "2_2") (pintype "unspecified"))
      (node (ref "R10") (pin "1") (pinfunction "1_1") (pintype "input"))
      (node (ref "U10") (pin "2") (pinfunction "DATA_2") (pintype "unspecified"))
    )
    (net (code "78") (name "Net-(U12-E)") (class "Default")
      (node (ref "R11") (pin "1") (pinfunction "1_1") (pintype "input"))
      (node (ref "R12") (pin "2") (pinfunction "2_2") (pintype "input"))
      (node (ref "U12") (pin "1") (pinfunction "E_1") (pintype "unspecified"))
    )
    (net (code "79") (name "Net-(USB1-D+)") (class "Default")
      (node (ref "R9") (pin "1") (pinfunction "1_1") (pintype "input"))
      (node (ref "USB1") (pin "3") (pinfunction "D+_3") (pintype "input"))
    )
    (net (code "80") (name "Net-(USB1-D-)") (class "Default")
      (node (ref "R8") (pin "1") (pinfunction "1_1") (pintype "input"))
      (node (ref "USB1") (pin "2") (pinfunction "D-_2") (pintype "input"))
    )
    (net (code "81") (name "VCC3V3") (class "Default")
      (node (ref "C14") (pin "2") (pinfunction "2_2") (pintype "input"))
      (node (ref "C3") (pin "2") (pinfunction "2_2") (pintype "unspecified"))
      (node (ref "C4") (pin "2") (pinfunction "2_2") (pintype "input"))
      (node (ref "CN1") (pin "1") (pinfunction "1_1") (pintype "unspecified"))
      (node (ref "CN1") (pin "2") (pinfunction "2_2") (pintype "unspecified"))
      (node (ref "D3") (pin "1") (pinfunction "A_1") (pintype "unspecified"))
      (node (ref "H1") (pin "1") (pinfunction "1_1") (pintype "unspecified"))
      (node (ref "H6") (pin "1") (pinfunction "1_1") (pintype "unspecified"))
      (node (ref "H7") (pin "2") (pinfunction "2_2") (pintype "unspecified"))
      (node (ref "H8") (pin "9") (pinfunction "9_9") (pintype "unspecified"))
      (node (ref "KEY2") (pin "1") (pinfunction "1_1") (pintype "input"))
      (node (ref "LED1") (pin "2") (pinfunction "A_2") (pintype "input"))
      (node (ref "R10") (pin "2") (pinfunction "2_2") (pintype "input"))
      (node (ref "R11") (pin "2") (pinfunction "2_2") (pintype "input"))
      (node (ref "R6") (pin "2") (pinfunction "2_2") (pintype "input"))
      (node (ref "R7") (pin "2") (pinfunction "2_2") (pintype "input"))
      (node (ref "U1") (pin "24") (pinfunction "VDD_1_24") (pintype "unspecified"))
      (node (ref "U1") (pin "36") (pinfunction "VDD_2_36") (pintype "unspecified"))
      (node (ref "U1") (pin "48") (pinfunction "VDD_3_48") (pintype "unspecified"))
      (node (ref "U1") (pin "9") (pinfunction "VDDA_9") (pintype "unspecified"))
      (node (ref "U10") (pin "1") (pinfunction "VDD_1") (pintype "unspecified"))
      (node (ref "U14") (pin "1") (pinfunction "1_1") (pintype "unspecified"))
      (node (ref "U18") (pin "1") (pinfunction "1_1") (pintype "unspecified"))
      (node (ref "U19") (pin "2") (pinfunction "2_2") (pintype "unspecified"))
      (node (ref "U2") (pin "5") (pinfunction "VOUT_5") (pintype "unspecified"))
      (node (ref "U20") (pin "2") (pinfunction "2_2") (pintype "unspecified"))
      (node (ref "U9") (pin "20") (pinfunction "VCC_20") (pintype "unspecified"))
    )
    (net (code "82") (name "VCC_BAT") (class "Default")
      (node (ref "D3") (pin "2") (pinfunction "K_2") (pintype "unspecified"))
      (node (ref "D4") (pin "2") (pinfunction "K_2") (pintype "unspecified"))
      (node (ref "U1") (pin "1") (pinfunction "VBAT_1") (pintype "unspecified"))
      (node (ref "U13") (pin "1") (pinfunction "1_1") (pintype "unspecified"))
      (node (ref "U21") (pin "1") (pinfunction "1_1") (pintype "unspecified"))
    )
    (net (code "83") (name "unconnected-(H9-Pad1)") (class "Default")
      (node (ref "H9") (pin "1") (pinfunction "1_1") (pintype "unspecified"))
    )
    (net (code "84") (name "unconnected-(H9-Pad2)") (class "Default")
      (node (ref "H9") (pin "2") (pinfunction "2_2") (pintype "unspecified"))
    )
    (net (code "85") (name "unconnected-(H9-Pad3)") (class "Default")
      (node (ref "H9") (pin "3") (pinfunction "3_3") (pintype "unspecified"))
    )
    (net (code "86") (name "unconnected-(H9-Pad4)") (class "Default")
      (node (ref "H9") (pin "4") (pinfunction "4_4") (pintype "unspecified"))
    )
    (net (code "87") (name "unconnected-(H9-Pad5)") (class "Default")
      (node (ref "H9") (pin "5") (pinfunction "5_5") (pintype "unspecified"))
    )
    (net (code "88") (name "unconnected-(H9-Pad6)") (class "Default")
      (node (ref "H9") (pin "6") (pinfunction "6_6") (pintype "unspecified"))
    )
    (net (code "89") (name "unconnected-(H9-Pad7)") (class "Default")
      (node (ref "H9") (pin "7") (pinfunction "7_7") (pintype "unspecified"))
    )
    (net (code "90") (name "unconnected-(H9-Pad8)") (class "Default")
      (node (ref "H9") (pin "8") (pinfunction "8_8") (pintype "unspecified"))
    )
    (net (code "91") (name "unconnected-(H9-Pad9)") (class "Default")
      (node (ref "H9") (pin "9") (pinfunction "9_9") (pintype "unspecified"))
    )
    (net (code "92") (name "unconnected-(H9-Pad10)") (class "Default")
      (node (ref "H9") (pin "10") (pinfunction "10_10") (pintype "unspecified"))
    )
    (net (code "93") (name "unconnected-(H9-Pad11)") (class "Default")
      (node (ref "H9") (pin "11") (pinfunction "11_11") (pintype "unspecified"))
    )
    (net (code "94") (name "unconnected-(H9-Pad12)") (class "Default")
      (node (ref "H9") (pin "12") (pinfunction "12_12") (pintype "unspecified"))
    )
    (net (code "95") (name "unconnected-(H9-Pad13)") (class "Default")
      (node (ref "H9") (pin "13") (pinfunction "13_13") (pintype "unspecified"))
    )
    (net (code "96") (name "unconnected-(H9-Pad14)") (class "Default")
      (node (ref "H9") (pin "14") (pinfunction "14_14") (pintype "unspecified"))
    )
    (net (code "97") (name "unconnected-(H9-Pad15)") (class "Default")
      (node (ref "H9") (pin "15") (pinfunction "15_15") (pintype "unspecified"))
    )
    (net (code "98") (name "unconnected-(H9-Pad16)") (class "Default")
      (node (ref "H9") (pin "16") (pinfunction "16_16") (pintype "unspecified"))
    )
    (net (code "99") (name "unconnected-(H9-Pad17)") (class "Default")
      (node (ref "H9") (pin "17") (pinfunction "17_17") (pintype "unspecified"))
    )
    (net (code "100") (name "unconnected-(U2-NC-Pad4)") (class "Default")
      (node (ref "U2") (pin "4") (pinfunction "NC_4") (pintype "unspecified+no_connect"))
    )
    (net (code "101") (name "unconnected-(U10-NC-Pad3)") (class "Default")
      (node (ref "U10") (pin "3") (pinfunction "NC_3") (pintype "unspecified"))
    )
    (net (code "102") (name "unconnected-(USB1-EH-Pad6)") (class "Default")
      (node (ref "USB1") (pin "6") (pinfunction "EH_6") (pintype "input+no_connect"))
    )
    (net (code "103") (name "unconnected-(USB1-ID-Pad4)") (class "Default")
      (node (ref "USB1") (pin "4") (pinfunction "ID_4") (pintype "input+no_connect"))
    )
  )
)
